# mainBoard.net
KiCad netlist of a schematic drawn in EAGLE
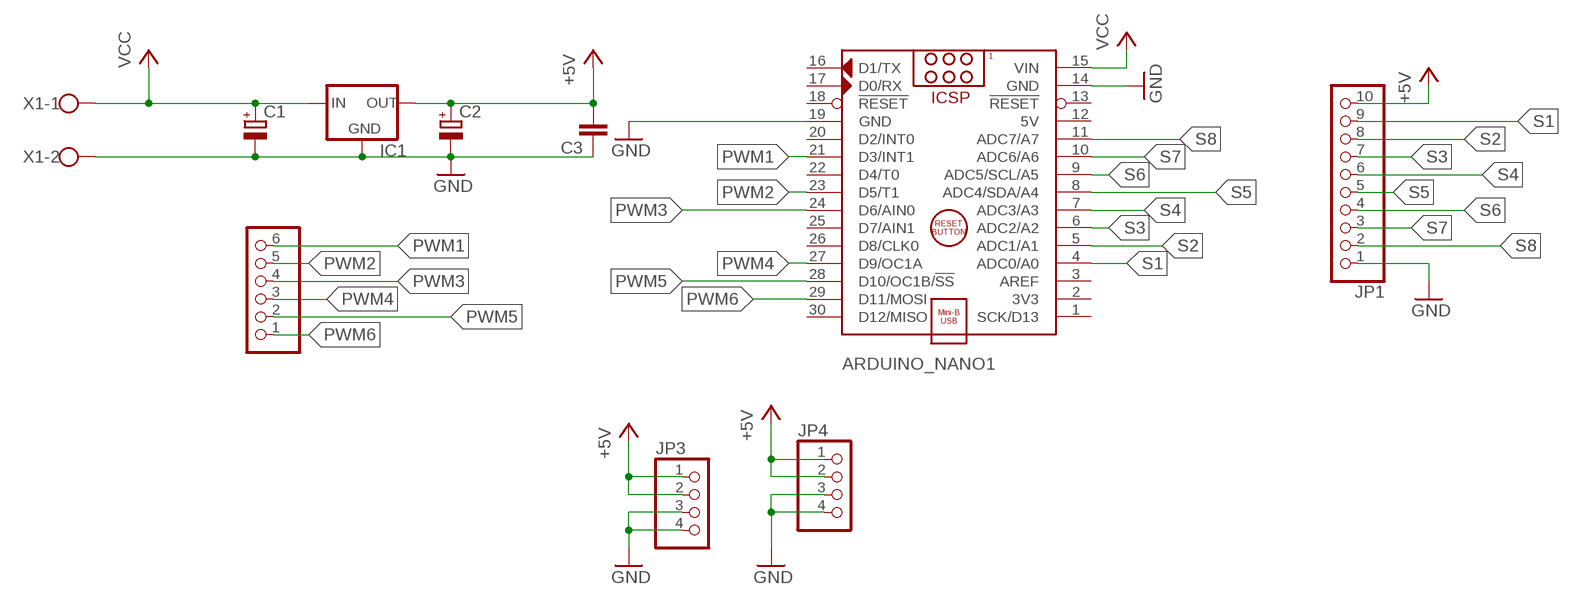
[diagram p0: schematic, sheet 1]

(export (version "E")
  (design (tool "Eeschema 10.0.6"))
  (components
    (comp (ref "ARDUINO_NANO1")
      (value "ARDUINO_NANO")
      (footprint "eagle-import:ARDUINO_NANO")
      (libsource (lib "eagle-import") (part "ARDUINO_NANO"))
    )
    (comp (ref "C1")
      (value "CPOL-EUE2-5")
      (footprint "eagle-import:E2-5")
      (libsource (lib "eagle-import") (part "CPOL-EUE2-5"))
    )
    (comp (ref "C2")
      (value "CPOL-EUE2-5")
      (footprint "eagle-import:E2-5")
      (libsource (lib "eagle-import") (part "CPOL-EUE2-5"))
    )
    (comp (ref "C3")
      (value "C-EU050-025X075")
      (footprint "eagle-import:C050-025X075")
      (libsource (lib "eagle-import") (part "C-EU050-025X075"))
    )
    (comp (ref "IC1")
      (value "78MXXS")
      (footprint "eagle-import:78MXXS")
      (libsource (lib "eagle-import") (part "78MXXS"))
    )
    (comp (ref "JP1")
      (value "PINHD-1X10")
      (footprint "eagle-import:1X10")
      (libsource (lib "eagle-import") (part "PINHD-1X10"))
    )
    (comp (ref "JP2")
      (value "PINHD-1X6")
      (footprint "eagle-import:1X06")
      (libsource (lib "eagle-import") (part "PINHD-1X6"))
    )
    (comp (ref "JP3")
      (value "PINHD-1X4")
      (footprint "eagle-import:1X04")
      (libsource (lib "eagle-import") (part "PINHD-1X4"))
    )
    (comp (ref "JP4")
      (value "PINHD-1X4")
      (footprint "eagle-import:1X04")
      (libsource (lib "eagle-import") (part "PINHD-1X4"))
    )
    (comp (ref "X1")
      (value "W237-102")
      (footprint "eagle-import:W237-102")
      (fields (field (name "MPN") "237-102"))
      (libsource (lib "eagle-import") (part "W237-102"))
    )
  )
  (nets
    (net (code "1") (name "+5V") (class "Default")
      (node (ref "C2") (pin "+") (pinfunction "+_+") (pintype "passive"))
      (node (ref "C3") (pin "2") (pinfunction "2_2") (pintype "passive"))
      (node (ref "IC1") (pin "OUT") (pinfunction "OUT_OUT") (pintype "passive"))
      (node (ref "JP1") (pin "10") (pinfunction "10_10") (pintype "passive"))
      (node (ref "JP3") (pin "1") (pinfunction "1_1") (pintype "passive"))
      (node (ref "JP3") (pin "2") (pinfunction "2_2") (pintype "passive"))
      (node (ref "JP4") (pin "1") (pinfunction "1_1") (pintype "passive"))
      (node (ref "JP4") (pin "2") (pinfunction "2_2") (pintype "passive"))
    )
    (net (code "2") (name "/5V") (class "Default")
      (node (ref "ARDUINO_NANO1") (pin "12") (pinfunction "5V_12") (pintype "power_in"))
    )
    (net (code "3") (name "GND") (class "Default")
      (node (ref "ARDUINO_NANO1") (pin "14") (pinfunction "GND_14") (pintype "power_in"))
      (node (ref "ARDUINO_NANO1") (pin "19") (pinfunction "GND_19") (pintype "power_in"))
      (node (ref "C1") (pin "-") (pinfunction "-_-") (pintype "passive"))
      (node (ref "C2") (pin "-") (pinfunction "-_-") (pintype "passive"))
      (node (ref "C3") (pin "1") (pinfunction "1_1") (pintype "passive"))
      (node (ref "IC1") (pin "GND") (pinfunction "GND_GND") (pintype "input"))
      (node (ref "JP1") (pin "1") (pinfunction "1_1") (pintype "passive"))
      (node (ref "JP3") (pin "3") (pinfunction "3_3") (pintype "passive"))
      (node (ref "JP3") (pin "4") (pinfunction "4_4") (pintype "passive"))
      (node (ref "JP4") (pin "3") (pinfunction "3_3") (pintype "passive"))
      (node (ref "JP4") (pin "4") (pinfunction "4_4") (pintype "passive"))
      (node (ref "X1") (pin "2") (pinfunction "KL_2") (pintype "passive"))
    )
    (net (code "4") (name "PWM1") (class "Default")
      (node (ref "ARDUINO_NANO1") (pin "21") (pinfunction "D3/INT1_21") (pintype "bidirectional"))
      (node (ref "JP2") (pin "6") (pinfunction "6_6") (pintype "passive"))
    )
    (net (code "5") (name "PWM2") (class "Default")
      (node (ref "ARDUINO_NANO1") (pin "23") (pinfunction "D5/T1_23") (pintype "bidirectional"))
      (node (ref "JP2") (pin "5") (pinfunction "5_5") (pintype "passive"))
    )
    (net (code "6") (name "PWM3") (class "Default")
      (node (ref "ARDUINO_NANO1") (pin "24") (pinfunction "D6/AIN0_24") (pintype "bidirectional"))
      (node (ref "JP2") (pin "4") (pinfunction "4_4") (pintype "passive"))
    )
    (net (code "7") (name "PWM4") (class "Default")
      (node (ref "ARDUINO_NANO1") (pin "27") (pinfunction "D9/OC1A_27") (pintype "bidirectional"))
      (node (ref "JP2") (pin "3") (pinfunction "3_3") (pintype "passive"))
    )
    (net (code "8") (name "PWM5") (class "Default")
      (node (ref "ARDUINO_NANO1") (pin "28") (pinfunction "D10/OC1B/~{SS}_28") (pintype "bidirectional"))
      (node (ref "JP2") (pin "2") (pinfunction "2_2") (pintype "passive"))
    )
    (net (code "9") (name "PWM6") (class "Default")
      (node (ref "ARDUINO_NANO1") (pin "29") (pinfunction "D11/MOSI_29") (pintype "bidirectional"))
      (node (ref "JP2") (pin "1") (pinfunction "1_1") (pintype "passive"))
    )
    (net (code "10") (name "S1") (class "Default")
      (node (ref "ARDUINO_NANO1") (pin "4") (pinfunction "ADC0/A0_4") (pintype "bidirectional"))
      (node (ref "JP1") (pin "9") (pinfunction "9_9") (pintype "passive"))
    )
    (net (code "11") (name "S2") (class "Default")
      (node (ref "ARDUINO_NANO1") (pin "5") (pinfunction "ADC1/A1_5") (pintype "bidirectional"))
      (node (ref "JP1") (pin "8") (pinfunction "8_8") (pintype "passive"))
    )
    (net (code "12") (name "S3") (class "Default")
      (node (ref "ARDUINO_NANO1") (pin "6") (pinfunction "ADC2/A2_6") (pintype "bidirectional"))
      (node (ref "JP1") (pin "7") (pinfunction "7_7") (pintype "passive"))
    )
    (net (code "13") (name "S4") (class "Default")
      (node (ref "ARDUINO_NANO1") (pin "7") (pinfunction "ADC3/A3_7") (pintype "bidirectional"))
      (node (ref "JP1") (pin "6") (pinfunction "6_6") (pintype "passive"))
    )
    (net (code "14") (name "S5") (class "Default")
      (node (ref "ARDUINO_NANO1") (pin "8") (pinfunction "ADC4/SDA/A4_8") (pintype "bidirectional"))
      (node (ref "JP1") (pin "5") (pinfunction "5_5") (pintype "passive"))
    )
    (net (code "15") (name "S6") (class "Default")
      (node (ref "ARDUINO_NANO1") (pin "9") (pinfunction "ADC5/SCL/A5_9") (pintype "bidirectional"))
      (node (ref "JP1") (pin "4") (pinfunction "4_4") (pintype "passive"))
    )
    (net (code "16") (name "S7") (class "Default")
      (node (ref "ARDUINO_NANO1") (pin "10") (pinfunction "ADC6/A6_10") (pintype "bidirectional"))
      (node (ref "JP1") (pin "3") (pinfunction "3_3") (pintype "passive"))
    )
    (net (code "17") (name "S8") (class "Default")
      (node (ref "ARDUINO_NANO1") (pin "11") (pinfunction "ADC7/A7_11") (pintype "bidirectional"))
      (node (ref "JP1") (pin "2") (pinfunction "2_2") (pintype "passive"))
    )
    (net (code "18") (name "VCC") (class "Default")
      (node (ref "ARDUINO_NANO1") (pin "15") (pinfunction "VIN_15") (pintype "power_in"))
      (node (ref "C1") (pin "+") (pinfunction "+_+") (pintype "passive"))
      (node (ref "IC1") (pin "IN") (pinfunction "IN_IN") (pintype "input"))
      (node (ref "X1") (pin "1") (pinfunction "KL_1") (pintype "passive"))
    )
    (net (code "19") (name "unconnected-(ARDUINO_NANO1-3V3-Pad2)") (class "Default")
      (node (ref "ARDUINO_NANO1") (pin "2") (pinfunction "3V3_2") (pintype "output"))
    )
    (net (code "20") (name "unconnected-(ARDUINO_NANO1-AREF-Pad3)") (class "Default")
      (node (ref "ARDUINO_NANO1") (pin "3") (pinfunction "AREF_3") (pintype "input"))
    )
    (net (code "21") (name "unconnected-(ARDUINO_NANO1-D0{slash}RX-Pad17)") (class "Default")
      (node (ref "ARDUINO_NANO1") (pin "17") (pinfunction "D0/RX_17") (pintype "bidirectional"))
    )
    (net (code "22") (name "unconnected-(ARDUINO_NANO1-D1{slash}TX-Pad16)") (class "Default")
      (node (ref "ARDUINO_NANO1") (pin "16") (pinfunction "D1/TX_16") (pintype "bidirectional"))
    )
    (net (code "23") (name "unconnected-(ARDUINO_NANO1-D2{slash}INT0-Pad20)") (class "Default")
      (node (ref "ARDUINO_NANO1") (pin "20") (pinfunction "D2/INT0_20") (pintype "bidirectional"))
    )
    (net (code "24") (name "unconnected-(ARDUINO_NANO1-D4{slash}T0-Pad22)") (class "Default")
      (node (ref "ARDUINO_NANO1") (pin "22") (pinfunction "D4/T0_22") (pintype "bidirectional"))
    )
    (net (code "25") (name "unconnected-(ARDUINO_NANO1-D7{slash}AIN1-Pad25)") (class "Default")
      (node (ref "ARDUINO_NANO1") (pin "25") (pinfunction "D7/AIN1_25") (pintype "bidirectional"))
    )
    (net (code "26") (name "unconnected-(ARDUINO_NANO1-D8{slash}CLK0-Pad26)") (class "Default")
      (node (ref "ARDUINO_NANO1") (pin "26") (pinfunction "D8/CLK0_26") (pintype "bidirectional"))
    )
    (net (code "27") (name "unconnected-(ARDUINO_NANO1-D12{slash}MISO-Pad30)") (class "Default")
      (node (ref "ARDUINO_NANO1") (pin "30") (pinfunction "D12/MISO_30") (pintype "bidirectional"))
    )
    (net (code "28") (name "unconnected-(ARDUINO_NANO1-SCK{slash}D13-Pad1)") (class "Default")
      (node (ref "ARDUINO_NANO1") (pin "1") (pinfunction "SCK/D13_1") (pintype "bidirectional"))
    )
    (net (code "29") (name "unconnected-(ARDUINO_NANO1-~{RESET}-Pad13)") (class "Default")
      (node (ref "ARDUINO_NANO1") (pin "13") (pinfunction "~{RESET}_13") (pintype "input"))
    )
    (net (code "30") (name "unconnected-(ARDUINO_NANO1-~{RESET}-Pad18)") (class "Default")
      (node (ref "ARDUINO_NANO1") (pin "18") (pinfunction "~{RESET}_18") (pintype "input"))
    )
  )
)
